# ArtixPower.net
KiCad netlist of a schematic drawn in Altium Designer
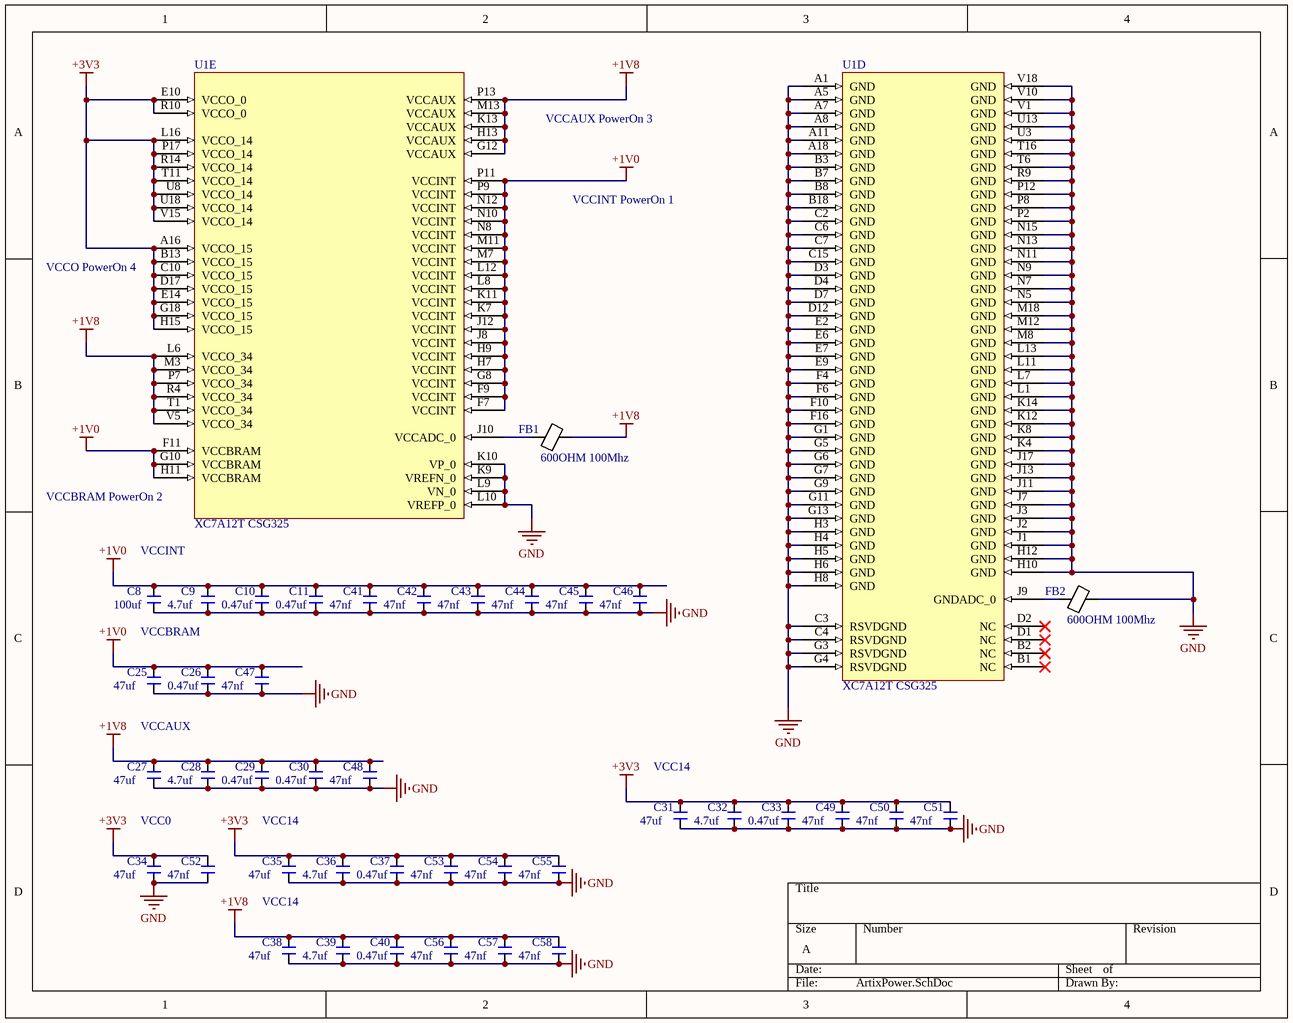
[diagram p0: ArtixPower.SchDoc]

(export (version "E")
  (design (tool "Eeschema 10.0.6"))
  (components
    (comp (ref "C8")
      (value "100uf")
      (footprint "1206")
      (description "1206")
      (libsource (lib "Capacitors") (part "100uf_1206"))
    )
    (comp (ref "C9")
      (value "4.7uf")
      (footprint "0402Footprint")
      (description "0402")
      (libsource (lib "Capacitors") (part "4.7uf_0402"))
    )
    (comp (ref "C10")
      (value "0.47uf")
      (footprint "0402Footprint")
      (description "0402")
      (libsource (lib "Capacitors") (part "0.47uf_0402"))
    )
    (comp (ref "C11")
      (value "0.47uf")
      (footprint "0402Footprint")
      (description "0402")
      (libsource (lib "Capacitors") (part "0.47uf_0402"))
    )
    (comp (ref "C25")
      (value "47uf")
      (footprint "0805FOOTPRINT")
      (description "0805")
      (libsource (lib "Capacitors") (part "47uf_0805"))
    )
    (comp (ref "C26")
      (value "0.47uf")
      (footprint "0402Footprint")
      (description "0402")
      (libsource (lib "Capacitors") (part "0.47uf_0402"))
    )
    (comp (ref "C27")
      (value "47uf")
      (footprint "0805FOOTPRINT")
      (description "0805")
      (libsource (lib "Capacitors") (part "47uf_0805"))
    )
    (comp (ref "C28")
      (value "4.7uf")
      (footprint "0402Footprint")
      (description "0402")
      (libsource (lib "Capacitors") (part "4.7uf_0402"))
    )
    (comp (ref "C29")
      (value "0.47uf")
      (footprint "0402Footprint")
      (description "0402")
      (libsource (lib "Capacitors") (part "0.47uf_0402"))
    )
    (comp (ref "C30")
      (value "0.47uf")
      (footprint "0402Footprint")
      (description "0402")
      (libsource (lib "Capacitors") (part "0.47uf_0402"))
    )
    (comp (ref "C31")
      (value "47uf")
      (footprint "0805FOOTPRINT")
      (description "0805")
      (libsource (lib "Capacitors") (part "47uf_0805"))
    )
    (comp (ref "C32")
      (value "4.7uf")
      (footprint "0402Footprint")
      (description "0402")
      (libsource (lib "Capacitors") (part "4.7uf_0402"))
    )
    (comp (ref "C33")
      (value "0.47uf")
      (footprint "0402Footprint")
      (description "0402")
      (libsource (lib "Capacitors") (part "0.47uf_0402"))
    )
    (comp (ref "C34")
      (value "47uf")
      (footprint "0805FOOTPRINT")
      (description "0805")
      (libsource (lib "Capacitors") (part "47uf_0805"))
    )
    (comp (ref "C35")
      (value "47uf")
      (footprint "0805FOOTPRINT")
      (description "0805")
      (libsource (lib "Capacitors") (part "47uf_0805"))
    )
    (comp (ref "C36")
      (value "4.7uf")
      (footprint "0402Footprint")
      (description "0402")
      (libsource (lib "Capacitors") (part "4.7uf_0402"))
    )
    (comp (ref "C37")
      (value "0.47uf")
      (footprint "0402Footprint")
      (description "0402")
      (libsource (lib "Capacitors") (part "0.47uf_0402"))
    )
    (comp (ref "C38")
      (value "47uf")
      (footprint "0805FOOTPRINT")
      (description "0805")
      (libsource (lib "Capacitors") (part "47uf_0805"))
    )
    (comp (ref "C39")
      (value "4.7uf")
      (footprint "0402Footprint")
      (description "0402")
      (libsource (lib "Capacitors") (part "4.7uf_0402"))
    )
    (comp (ref "C40")
      (value "0.47uf")
      (footprint "0402Footprint")
      (description "0402")
      (libsource (lib "Capacitors") (part "0.47uf_0402"))
    )
    (comp (ref "C41")
      (value "47nf")
      (footprint "0402Footprint")
      (description "0402")
      (libsource (lib "Capacitors") (part "47nf_0402"))
    )
    (comp (ref "C42")
      (value "47nf")
      (footprint "0402Footprint")
      (description "0402")
      (libsource (lib "Capacitors") (part "47nf_0402"))
    )
    (comp (ref "C43")
      (value "47nf")
      (footprint "0402Footprint")
      (description "0402")
      (libsource (lib "Capacitors") (part "47nf_0402"))
    )
    (comp (ref "C44")
      (value "47nf")
      (footprint "0402Footprint")
      (description "0402")
      (libsource (lib "Capacitors") (part "47nf_0402"))
    )
    (comp (ref "C45")
      (value "47nf")
      (footprint "0402Footprint")
      (description "0402")
      (libsource (lib "Capacitors") (part "47nf_0402"))
    )
    (comp (ref "C46")
      (value "47nf")
      (footprint "0402Footprint")
      (description "0402")
      (libsource (lib "Capacitors") (part "47nf_0402"))
    )
    (comp (ref "C47")
      (value "47nf")
      (footprint "0402Footprint")
      (description "0402")
      (libsource (lib "Capacitors") (part "47nf_0402"))
    )
    (comp (ref "C48")
      (value "47nf")
      (footprint "0402Footprint")
      (description "0402")
      (libsource (lib "Capacitors") (part "47nf_0402"))
    )
    (comp (ref "C49")
      (value "47nf")
      (footprint "0402Footprint")
      (description "0402")
      (libsource (lib "Capacitors") (part "47nf_0402"))
    )
    (comp (ref "C50")
      (value "47nf")
      (footprint "0402Footprint")
      (description "0402")
      (libsource (lib "Capacitors") (part "47nf_0402"))
    )
    (comp (ref "C51")
      (value "47nf")
      (footprint "0402Footprint")
      (description "0402")
      (libsource (lib "Capacitors") (part "47nf_0402"))
    )
    (comp (ref "C52")
      (value "47nf")
      (footprint "0402Footprint")
      (description "0402")
      (libsource (lib "Capacitors") (part "47nf_0402"))
    )
    (comp (ref "C53")
      (value "47nf")
      (footprint "0402Footprint")
      (description "0402")
      (libsource (lib "Capacitors") (part "47nf_0402"))
    )
    (comp (ref "C54")
      (value "47nf")
      (footprint "0402Footprint")
      (description "0402")
      (libsource (lib "Capacitors") (part "47nf_0402"))
    )
    (comp (ref "C55")
      (value "47nf")
      (footprint "0402Footprint")
      (description "0402")
      (libsource (lib "Capacitors") (part "47nf_0402"))
    )
    (comp (ref "C56")
      (value "47nf")
      (footprint "0402Footprint")
      (description "0402")
      (libsource (lib "Capacitors") (part "47nf_0402"))
    )
    (comp (ref "C57")
      (value "47nf")
      (footprint "0402Footprint")
      (description "0402")
      (libsource (lib "Capacitors") (part "47nf_0402"))
    )
    (comp (ref "C58")
      (value "47nf")
      (footprint "0402Footprint")
      (description "0402")
      (libsource (lib "Capacitors") (part "47nf_0402"))
    )
    (comp (ref "FB1")
      (value "600OHM 100Mhz")
      (footprint "0805")
      (description "FERRITE BEAD 600 OHM 0805")
      (libsource (lib "Inductors") (part "HZ0805E601R-10"))
    )
    (comp (ref "FB2")
      (value "600OHM 100Mhz")
      (footprint "0805")
      (description "FERRITE BEAD 600 OHM 0805")
      (libsource (lib "Inductors") (part "HZ0805E601R-10"))
    )
    (comp (ref "U1")
      (value "XC7A12T CSG325")
      (footprint "BGA324C80P18X18_1500X1500X150")
      (libsource (lib "XC7A12T_1CPG238I") (part "XC7A12T_1CSG325I"))
    )
  )
  (nets
    (net (code "1") (name "+1V0") (class "Default")
      (node (ref "C10") (pin "1") (pinfunction "1_1") (pintype "passive"))
      (node (ref "C11") (pin "1") (pinfunction "1_1") (pintype "passive"))
      (node (ref "C25") (pin "1") (pinfunction "1_1") (pintype "passive"))
      (node (ref "C26") (pin "1") (pinfunction "1_1") (pintype "passive"))
      (node (ref "C41") (pin "1") (pinfunction "1_1") (pintype "passive"))
      (node (ref "C42") (pin "1") (pinfunction "1_1") (pintype "passive"))
      (node (ref "C43") (pin "1") (pinfunction "1_1") (pintype "passive"))
      (node (ref "C44") (pin "1") (pinfunction "1_1") (pintype "passive"))
      (node (ref "C45") (pin "1") (pinfunction "1_1") (pintype "passive"))
      (node (ref "C46") (pin "1") (pinfunction "1_1") (pintype "passive"))
      (node (ref "C47") (pin "1") (pinfunction "1_1") (pintype "passive"))
      (node (ref "C8") (pin "1") (pinfunction "1_1") (pintype "passive"))
      (node (ref "C9") (pin "1") (pinfunction "1_1") (pintype "passive"))
      (node (ref "U1") (pin "F11") (pinfunction "VCCBRAM_F11") (pintype "input"))
      (node (ref "U1") (pin "F7") (pinfunction "VCCINT_F7") (pintype "input"))
      (node (ref "U1") (pin "F9") (pinfunction "VCCINT_F9") (pintype "input"))
      (node (ref "U1") (pin "G10") (pinfunction "VCCBRAM_G10") (pintype "input"))
      (node (ref "U1") (pin "G8") (pinfunction "VCCINT_G8") (pintype "input"))
      (node (ref "U1") (pin "H11") (pinfunction "VCCBRAM_H11") (pintype "input"))
      (node (ref "U1") (pin "H7") (pinfunction "VCCINT_H7") (pintype "input"))
      (node (ref "U1") (pin "H9") (pinfunction "VCCINT_H9") (pintype "input"))
      (node (ref "U1") (pin "J12") (pinfunction "VCCINT_J12") (pintype "input"))
      (node (ref "U1") (pin "J8") (pinfunction "VCCINT_J8") (pintype "input"))
      (node (ref "U1") (pin "K11") (pinfunction "VCCINT_K11") (pintype "input"))
      (node (ref "U1") (pin "K7") (pinfunction "VCCINT_K7") (pintype "input"))
      (node (ref "U1") (pin "L12") (pinfunction "VCCINT_L12") (pintype "input"))
      (node (ref "U1") (pin "L8") (pinfunction "VCCINT_L8") (pintype "input"))
      (node (ref "U1") (pin "M11") (pinfunction "VCCINT_M11") (pintype "input"))
      (node (ref "U1") (pin "M7") (pinfunction "VCCINT_M7") (pintype "input"))
      (node (ref "U1") (pin "N10") (pinfunction "VCCINT_N10") (pintype "input"))
      (node (ref "U1") (pin "N12") (pinfunction "VCCINT_N12") (pintype "input"))
      (node (ref "U1") (pin "N8") (pinfunction "VCCINT_N8") (pintype "input"))
      (node (ref "U1") (pin "P11") (pinfunction "VCCINT_P11") (pintype "input"))
      (node (ref "U1") (pin "P9") (pinfunction "VCCINT_P9") (pintype "input"))
    )
    (net (code "2") (name "+1V8") (class "Default")
      (node (ref "C27") (pin "1") (pinfunction "1_1") (pintype "passive"))
      (node (ref "C28") (pin "1") (pinfunction "1_1") (pintype "passive"))
      (node (ref "C29") (pin "1") (pinfunction "1_1") (pintype "passive"))
      (node (ref "C30") (pin "1") (pinfunction "1_1") (pintype "passive"))
      (node (ref "C38") (pin "1") (pinfunction "1_1") (pintype "passive"))
      (node (ref "C39") (pin "1") (pinfunction "1_1") (pintype "passive"))
      (node (ref "C40") (pin "1") (pinfunction "1_1") (pintype "passive"))
      (node (ref "C48") (pin "1") (pinfunction "1_1") (pintype "passive"))
      (node (ref "C56") (pin "1") (pinfunction "1_1") (pintype "passive"))
      (node (ref "C57") (pin "1") (pinfunction "1_1") (pintype "passive"))
      (node (ref "C58") (pin "1") (pinfunction "1_1") (pintype "passive"))
      (node (ref "FB1") (pin "2") (pinfunction "2_2") (pintype "passive"))
      (node (ref "U1") (pin "G12") (pinfunction "VCCAUX_G12") (pintype "input"))
      (node (ref "U1") (pin "H13") (pinfunction "VCCAUX_H13") (pintype "input"))
      (node (ref "U1") (pin "K13") (pinfunction "VCCAUX_K13") (pintype "input"))
      (node (ref "U1") (pin "L6") (pinfunction "VCCO_34_L6") (pintype "input"))
      (node (ref "U1") (pin "M13") (pinfunction "VCCAUX_M13") (pintype "input"))
      (node (ref "U1") (pin "M3") (pinfunction "VCCO_34_M3") (pintype "input"))
      (node (ref "U1") (pin "P13") (pinfunction "VCCAUX_P13") (pintype "input"))
      (node (ref "U1") (pin "P7") (pinfunction "VCCO_34_P7") (pintype "input"))
      (node (ref "U1") (pin "R4") (pinfunction "VCCO_34_R4") (pintype "input"))
      (node (ref "U1") (pin "T1") (pinfunction "VCCO_34_T1") (pintype "input"))
      (node (ref "U1") (pin "V5") (pinfunction "VCCO_34_V5") (pintype "input"))
    )
    (net (code "3") (name "+3V3") (class "Default")
      (node (ref "C31") (pin "1") (pinfunction "1_1") (pintype "passive"))
      (node (ref "C32") (pin "1") (pinfunction "1_1") (pintype "passive"))
      (node (ref "C33") (pin "1") (pinfunction "1_1") (pintype "passive"))
      (node (ref "C34") (pin "1") (pinfunction "1_1") (pintype "passive"))
      (node (ref "C35") (pin "1") (pinfunction "1_1") (pintype "passive"))
      (node (ref "C36") (pin "1") (pinfunction "1_1") (pintype "passive"))
      (node (ref "C37") (pin "1") (pinfunction "1_1") (pintype "passive"))
      (node (ref "C49") (pin "1") (pinfunction "1_1") (pintype "passive"))
      (node (ref "C50") (pin "1") (pinfunction "1_1") (pintype "passive"))
      (node (ref "C51") (pin "1") (pinfunction "1_1") (pintype "passive"))
      (node (ref "C52") (pin "1") (pinfunction "1_1") (pintype "passive"))
      (node (ref "C53") (pin "1") (pinfunction "1_1") (pintype "passive"))
      (node (ref "C54") (pin "1") (pinfunction "1_1") (pintype "passive"))
      (node (ref "C55") (pin "1") (pinfunction "1_1") (pintype "passive"))
      (node (ref "U1") (pin "A16") (pinfunction "VCCO_15_A16") (pintype "input"))
      (node (ref "U1") (pin "B13") (pinfunction "VCCO_15_B13") (pintype "input"))
      (node (ref "U1") (pin "C10") (pinfunction "VCCO_15_C10") (pintype "input"))
      (node (ref "U1") (pin "D17") (pinfunction "VCCO_15_D17") (pintype "input"))
      (node (ref "U1") (pin "E10") (pinfunction "VCCO_0_E10") (pintype "input"))
      (node (ref "U1") (pin "E14") (pinfunction "VCCO_15_E14") (pintype "input"))
      (node (ref "U1") (pin "G18") (pinfunction "VCCO_15_G18") (pintype "input"))
      (node (ref "U1") (pin "H15") (pinfunction "VCCO_15_H15") (pintype "input"))
      (node (ref "U1") (pin "L16") (pinfunction "VCCO_14_L16") (pintype "input"))
      (node (ref "U1") (pin "P17") (pinfunction "VCCO_14_P17") (pintype "input"))
      (node (ref "U1") (pin "R10") (pinfunction "VCCO_0_R10") (pintype "input"))
      (node (ref "U1") (pin "R14") (pinfunction "VCCO_14_R14") (pintype "input"))
      (node (ref "U1") (pin "T11") (pinfunction "VCCO_14_T11") (pintype "input"))
      (node (ref "U1") (pin "U18") (pinfunction "VCCO_14_U18") (pintype "input"))
      (node (ref "U1") (pin "U8") (pinfunction "VCCO_14_U8") (pintype "input"))
      (node (ref "U1") (pin "V15") (pinfunction "VCCO_14_V15") (pintype "input"))
    )
    (net (code "4") (name "GND") (class "Default")
      (node (ref "C10") (pin "2") (pinfunction "2_2") (pintype "passive"))
      (node (ref "C11") (pin "2") (pinfunction "2_2") (pintype "passive"))
      (node (ref "C25") (pin "2") (pinfunction "2_2") (pintype "passive"))
      (node (ref "C26") (pin "2") (pinfunction "2_2") (pintype "passive"))
      (node (ref "C27") (pin "2") (pinfunction "2_2") (pintype "passive"))
      (node (ref "C28") (pin "2") (pinfunction "2_2") (pintype "passive"))
      (node (ref "C29") (pin "2") (pinfunction "2_2") (pintype "passive"))
      (node (ref "C30") (pin "2") (pinfunction "2_2") (pintype "passive"))
      (node (ref "C31") (pin "2") (pinfunction "2_2") (pintype "passive"))
      (node (ref "C32") (pin "2") (pinfunction "2_2") (pintype "passive"))
      (node (ref "C33") (pin "2") (pinfunction "2_2") (pintype "passive"))
      (node (ref "C34") (pin "2") (pinfunction "2_2") (pintype "passive"))
      (node (ref "C35") (pin "2") (pinfunction "2_2") (pintype "passive"))
      (node (ref "C36") (pin "2") (pinfunction "2_2") (pintype "passive"))
      (node (ref "C37") (pin "2") (pinfunction "2_2") (pintype "passive"))
      (node (ref "C38") (pin "2") (pinfunction "2_2") (pintype "passive"))
      (node (ref "C39") (pin "2") (pinfunction "2_2") (pintype "passive"))
      (node (ref "C40") (pin "2") (pinfunction "2_2") (pintype "passive"))
      (node (ref "C41") (pin "2") (pinfunction "2_2") (pintype "passive"))
      (node (ref "C42") (pin "2") (pinfunction "2_2") (pintype "passive"))
      (node (ref "C43") (pin "2") (pinfunction "2_2") (pintype "passive"))
      (node (ref "C44") (pin "2") (pinfunction "2_2") (pintype "passive"))
      (node (ref "C45") (pin "2") (pinfunction "2_2") (pintype "passive"))
      (node (ref "C46") (pin "2") (pinfunction "2_2") (pintype "passive"))
      (node (ref "C47") (pin "2") (pinfunction "2_2") (pintype "passive"))
      (node (ref "C48") (pin "2") (pinfunction "2_2") (pintype "passive"))
      (node (ref "C49") (pin "2") (pinfunction "2_2") (pintype "passive"))
      (node (ref "C50") (pin "2") (pinfunction "2_2") (pintype "passive"))
      (node (ref "C51") (pin "2") (pinfunction "2_2") (pintype "passive"))
      (node (ref "C52") (pin "2") (pinfunction "2_2") (pintype "passive"))
      (node (ref "C53") (pin "2") (pinfunction "2_2") (pintype "passive"))
      (node (ref "C54") (pin "2") (pinfunction "2_2") (pintype "passive"))
      (node (ref "C55") (pin "2") (pinfunction "2_2") (pintype "passive"))
      (node (ref "C56") (pin "2") (pinfunction "2_2") (pintype "passive"))
      (node (ref "C57") (pin "2") (pinfunction "2_2") (pintype "passive"))
      (node (ref "C58") (pin "2") (pinfunction "2_2") (pintype "passive"))
      (node (ref "C8") (pin "2") (pinfunction "2_2") (pintype "passive"))
      (node (ref "C9") (pin "2") (pinfunction "2_2") (pintype "passive"))
      (node (ref "FB2") (pin "2") (pinfunction "2_2") (pintype "passive"))
      (node (ref "U1") (pin "A1") (pinfunction "GND_A1") (pintype "input"))
      (node (ref "U1") (pin "A11") (pinfunction "GND_A11") (pintype "input"))
      (node (ref "U1") (pin "A18") (pinfunction "GND_A18") (pintype "input"))
      (node (ref "U1") (pin "A5") (pinfunction "GND_A5") (pintype "input"))
      (node (ref "U1") (pin "A7") (pinfunction "GND_A7") (pintype "input"))
      (node (ref "U1") (pin "A8") (pinfunction "GND_A8") (pintype "input"))
      (node (ref "U1") (pin "B18") (pinfunction "GND_B18") (pintype "input"))
      (node (ref "U1") (pin "B3") (pinfunction "GND_B3") (pintype "input"))
      (node (ref "U1") (pin "B7") (pinfunction "GND_B7") (pintype "input"))
      (node (ref "U1") (pin "B8") (pinfunction "GND_B8") (pintype "input"))
      (node (ref "U1") (pin "C15") (pinfunction "GND_C15") (pintype "input"))
      (node (ref "U1") (pin "C2") (pinfunction "GND_C2") (pintype "input"))
      (node (ref "U1") (pin "C3") (pinfunction "RSVDGND_C3") (pintype "input"))
      (node (ref "U1") (pin "C4") (pinfunction "RSVDGND_C4") (pintype "input"))
      (node (ref "U1") (pin "C6") (pinfunction "GND_C6") (pintype "input"))
      (node (ref "U1") (pin "C7") (pinfunction "GND_C7") (pintype "input"))
      (node (ref "U1") (pin "D12") (pinfunction "GND_D12") (pintype "input"))
      (node (ref "U1") (pin "D3") (pinfunction "GND_D3") (pintype "input"))
      (node (ref "U1") (pin "D4") (pinfunction "GND_D4") (pintype "input"))
      (node (ref "U1") (pin "D7") (pinfunction "GND_D7") (pintype "input"))
      (node (ref "U1") (pin "E2") (pinfunction "GND_E2") (pintype "input"))
      (node (ref "U1") (pin "E6") (pinfunction "GND_E6") (pintype "input"))
      (node (ref "U1") (pin "E7") (pinfunction "GND_E7") (pintype "input"))
      (node (ref "U1") (pin "E9") (pinfunction "GND_E9") (pintype "input"))
      (node (ref "U1") (pin "F10") (pinfunction "GND_F10") (pintype "input"))
      (node (ref "U1") (pin "F16") (pinfunction "GND_F16") (pintype "input"))
      (node (ref "U1") (pin "F4") (pinfunction "GND_F4") (pintype "input"))
      (node (ref "U1") (pin "F6") (pinfunction "GND_F6") (pintype "input"))
      (node (ref "U1") (pin "G1") (pinfunction "GND_G1") (pintype "input"))
      (node (ref "U1") (pin "G11") (pinfunction "GND_G11") (pintype "input"))
      (node (ref "U1") (pin "G13") (pinfunction "GND_G13") (pintype "input"))
      (node (ref "U1") (pin "G3") (pinfunction "RSVDGND_G3") (pintype "input"))
      (node (ref "U1") (pin "G4") (pinfunction "RSVDGND_G4") (pintype "input"))
      (node (ref "U1") (pin "G5") (pinfunction "GND_G5") (pintype "input"))
      (node (ref "U1") (pin "G6") (pinfunction "GND_G6") (pintype "input"))
      (node (ref "U1") (pin "G7") (pinfunction "GND_G7") (pintype "input"))
      (node (ref "U1") (pin "G9") (pinfunction "GND_G9") (pintype "input"))
      (node (ref "U1") (pin "H10") (pinfunction "GND_H10") (pintype "input"))
      (node (ref "U1") (pin "H12") (pinfunction "GND_H12") (pintype "input"))
      (node (ref "U1") (pin "H3") (pinfunction "GND_H3") (pintype "input"))
      (node (ref "U1") (pin "H4") (pinfunction "GND_H4") (pintype "input"))
      (node (ref "U1") (pin "H5") (pinfunction "GND_H5") (pintype "input"))
      (node (ref "U1") (pin "H6") (pinfunction "GND_H6") (pintype "input"))
      (node (ref "U1") (pin "H8") (pinfunction "GND_H8") (pintype "input"))
      (node (ref "U1") (pin "J1") (pinfunction "GND_J1") (pintype "input"))
      (node (ref "U1") (pin "J11") (pinfunction "GND_J11") (pintype "input"))
      (node (ref "U1") (pin "J13") (pinfunction "GND_J13") (pintype "input"))
      (node (ref "U1") (pin "J17") (pinfunction "GND_J17") (pintype "input"))
      (node (ref "U1") (pin "J2") (pinfunction "GND_J2") (pintype "input"))
      (node (ref "U1") (pin "J3") (pinfunction "GND_J3") (pintype "input"))
      (node (ref "U1") (pin "J7") (pinfunction "GND_J7") (pintype "input"))
      (node (ref "U1") (pin "K10") (pinfunction "VP_0_K10") (pintype "input"))
      (node (ref "U1") (pin "K12") (pinfunction "GND_K12") (pintype "input"))
      (node (ref "U1") (pin "K14") (pinfunction "GND_K14") (pintype "input"))
      (node (ref "U1") (pin "K4") (pinfunction "GND_K4") (pintype "input"))
      (node (ref "U1") (pin "K8") (pinfunction "GND_K8") (pintype "input"))
      (node (ref "U1") (pin "K9") (pinfunction "VREFN_0_K9") (pintype "input"))
      (node (ref "U1") (pin "L1") (pinfunction "GND_L1") (pintype "input"))
      (node (ref "U1") (pin "L10") (pinfunction "VREFP_0_L10") (pintype "input"))
      (node (ref "U1") (pin "L11") (pinfunction "GND_L11") (pintype "input"))
      (node (ref "U1") (pin "L13") (pinfunction "GND_L13") (pintype "input"))
      (node (ref "U1") (pin "L7") (pinfunction "GND_L7") (pintype "input"))
      (node (ref "U1") (pin "L9") (pinfunction "VN_0_L9") (pintype "input"))
      (node (ref "U1") (pin "M12") (pinfunction "GND_M12") (pintype "input"))
      (node (ref "U1") (pin "M18") (pinfunction "GND_M18") (pintype "input"))
      (node (ref "U1") (pin "M8") (pinfunction "GND_M8") (pintype "input"))
      (node (ref "U1") (pin "N11") (pinfunction "GND_N11") (pintype "input"))
      (node (ref "U1") (pin "N13") (pinfunction "GND_N13") (pintype "input"))
      (node (ref "U1") (pin "N15") (pinfunction "GND_N15") (pintype "input"))
      (node (ref "U1") (pin "N5") (pinfunction "GND_N5") (pintype "input"))
      (node (ref "U1") (pin "N7") (pinfunction "GND_N7") (pintype "input"))
      (node (ref "U1") (pin "N9") (pinfunction "GND_N9") (pintype "input"))
      (node (ref "U1") (pin "P12") (pinfunction "GND_P12") (pintype "input"))
      (node (ref "U1") (pin "P2") (pinfunction "GND_P2") (pintype "input"))
      (node (ref "U1") (pin "P8") (pinfunction "GND_P8") (pintype "input"))
      (node (ref "U1") (pin "R9") (pinfunction "GND_R9") (pintype "input"))
      (node (ref "U1") (pin "T16") (pinfunction "GND_T16") (pintype "input"))
      (node (ref "U1") (pin "T6") (pinfunction "GND_T6") (pintype "input"))
      (node (ref "U1") (pin "U13") (pinfunction "GND_U13") (pintype "input"))
      (node (ref "U1") (pin "U3") (pinfunction "GND_U3") (pintype "input"))
      (node (ref "U1") (pin "V1") (pinfunction "GND_V1") (pintype "input"))
      (node (ref "U1") (pin "V10") (pinfunction "GND_V10") (pintype "input"))
      (node (ref "U1") (pin "V18") (pinfunction "GND_V18") (pintype "input"))
    )
    (net (code "5") (name "Net-(U1D-GNDADC_0)") (class "Default")
      (node (ref "FB2") (pin "1") (pinfunction "1_1") (pintype "passive"))
      (node (ref "U1") (pin "J9") (pinfunction "GNDADC_0_J9") (pintype "input"))
    )
    (net (code "6") (name "Net-(U1E-VCCADC_0)") (class "Default")
      (node (ref "FB1") (pin "1") (pinfunction "1_1") (pintype "passive"))
      (node (ref "U1") (pin "J10") (pinfunction "VCCADC_0_J10") (pintype "input"))
    )
    (net (code "7") (name "unconnected-(U1D-NC-PadB1)") (class "Default")
      (node (ref "U1") (pin "B1") (pinfunction "NC_B1") (pintype "input+no_connect"))
    )
    (net (code "8") (name "unconnected-(U1D-NC-PadB2)") (class "Default")
      (node (ref "U1") (pin "B2") (pinfunction "NC_B2") (pintype "input+no_connect"))
    )
    (net (code "9") (name "unconnected-(U1D-NC-PadD1)") (class "Default")
      (node (ref "U1") (pin "D1") (pinfunction "NC_D1") (pintype "input+no_connect"))
    )
    (net (code "10") (name "unconnected-(U1D-NC-PadD2)") (class "Default")
      (node (ref "U1") (pin "D2") (pinfunction "NC_D2") (pintype "input+no_connect"))
    )
  )
)
